# ETAP.net
KiCad netlist of a schematic drawn in EAGLE
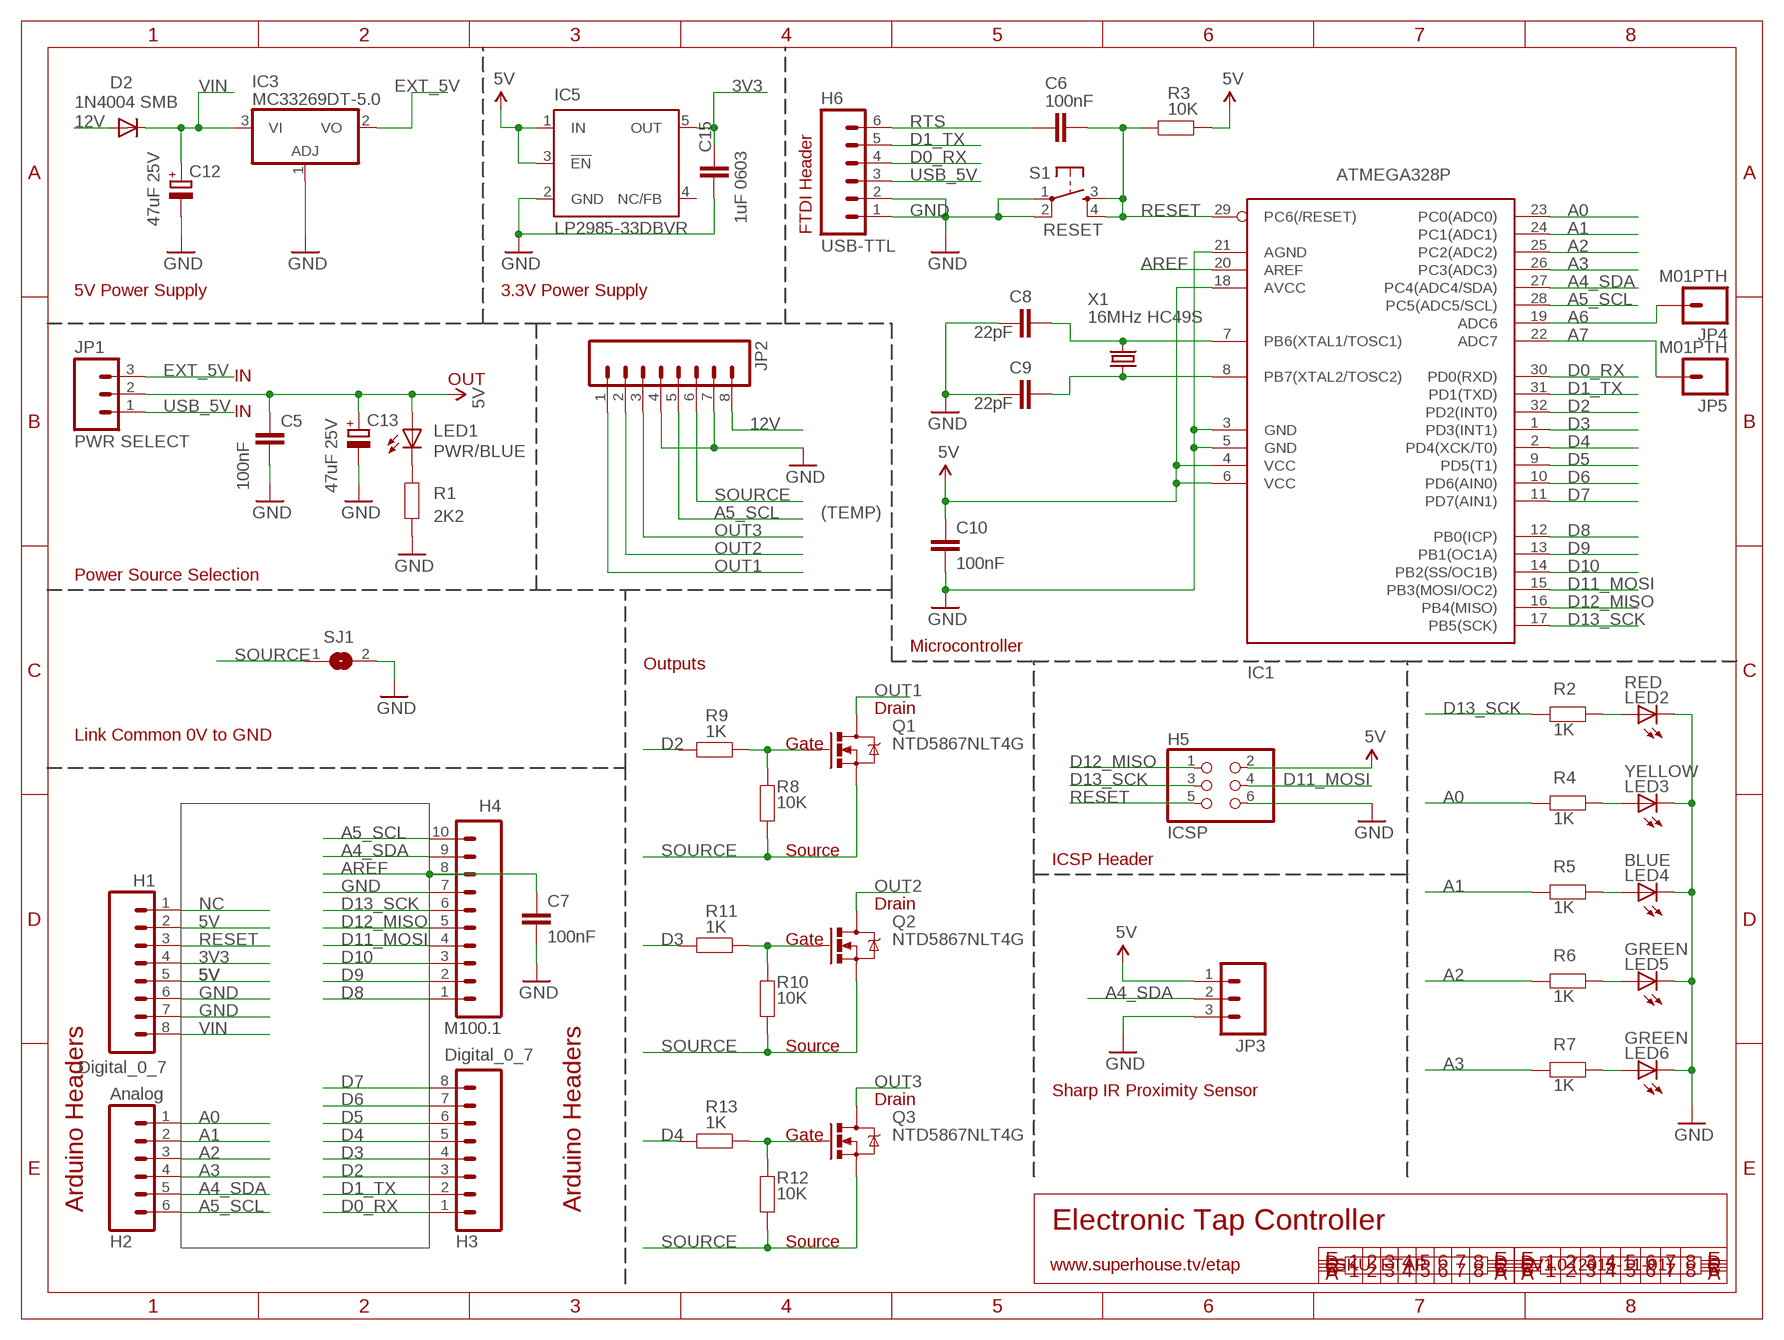
[diagram p0: schematic, sheet 1]

(export (version "E")
  (design (tool "Eeschema 10.0.6"))
  (components
    (comp (ref "C5")
      (value "100nF")
      (footprint "eagle-import:0603")
      (libsource (lib "eagle-import") (part "freetronics-master-v1.1_CAP0603"))
    )
    (comp (ref "C6")
      (value "100nF")
      (footprint "eagle-import:0603")
      (libsource (lib "eagle-import") (part "freetronics-master-v1.1_CAP0603"))
    )
    (comp (ref "C7")
      (value "100nF")
      (footprint "eagle-import:0603")
      (libsource (lib "eagle-import") (part "freetronics-master-v1.1_CAP0603"))
    )
    (comp (ref "C8")
      (value "22pF")
      (footprint "eagle-import:0603")
      (libsource (lib "eagle-import") (part "freetronics-master-v1.1_CAP0603"))
    )
    (comp (ref "C9")
      (value "22pF")
      (footprint "eagle-import:0603")
      (libsource (lib "eagle-import") (part "freetronics-master-v1.1_CAP0603"))
    )
    (comp (ref "C10")
      (value "100nF")
      (footprint "eagle-import:0603")
      (libsource (lib "eagle-import") (part "freetronics-master-v1.1_CAP0603"))
    )
    (comp (ref "C12")
      (value "47uF 25V")
      (footprint "eagle-import:PANASONIC_D")
      (libsource (lib "eagle-import") (part "CPOL-EUD"))
    )
    (comp (ref "C13")
      (value "47uF 25V")
      (footprint "eagle-import:PANASONIC_D")
      (libsource (lib "eagle-import") (part "CPOL-EUD"))
    )
    (comp (ref "C15")
      (value "1uF 0603")
      (footprint "eagle-import:0603")
      (libsource (lib "eagle-import") (part "CAP0603"))
    )
    (comp (ref "D2")
      (value "1N4004 SMB")
      (footprint "eagle-import:SMB-DIODE")
      (libsource (lib "eagle-import") (part "DIODESMB"))
    )
    (comp (ref "H1")
      (value "Digital_0_7")
      (footprint "eagle-import:1X08")
      (libsource (lib "eagle-import") (part "M08"))
    )
    (comp (ref "H2")
      (value "Analog")
      (footprint "eagle-import:1X06")
      (libsource (lib "eagle-import") (part "M06SIP"))
    )
    (comp (ref "H3")
      (value "Digital_0_7")
      (footprint "eagle-import:1X08")
      (libsource (lib "eagle-import") (part "M08"))
    )
    (comp (ref "H4")
      (value "M100.1")
      (footprint "eagle-import:1X10")
      (libsource (lib "eagle-import") (part "M100.1"))
    )
    (comp (ref "H5")
      (value "ICSP")
      (footprint "eagle-import:2X03")
      (libsource (lib "eagle-import") (part "PINHD-2X3"))
    )
    (comp (ref "H6")
      (value "USB-TTL")
      (footprint "eagle-import:1X06")
      (libsource (lib "eagle-import") (part "M06SIP"))
    )
    (comp (ref "IC1")
      (value "ATMEGA328P")
      (footprint "eagle-import:TQFP32-08")
      (libsource (lib "eagle-import") (part "AVR-MEGA8-AI"))
    )
    (comp (ref "IC3")
      (value "MC33269DT-5.0")
      (footprint "eagle-import:DPACK")
      (libsource (lib "eagle-import") (part "MC33269?D-5.0"))
    )
    (comp (ref "IC5")
      (value "LP2985-33DBVR")
      (footprint "eagle-import:TEXAS_SOT23-DBV")
      (libsource (lib "eagle-import") (part "TEXAS_TPS77033"))
    )
    (comp (ref "JP1")
      (value "PWR SELECT")
      (footprint "eagle-import:1X03")
      (libsource (lib "eagle-import") (part "M03PTH"))
    )
    (comp (ref "JP2")
      (value "M08STD")
      (footprint "eagle-import:1X08")
      (libsource (lib "eagle-import") (part "M08STD"))
    )
    (comp (ref "JP3")
      (value "M03PTH")
      (footprint "eagle-import:1X03")
      (libsource (lib "eagle-import") (part "freetronics-jon_M03PTH"))
    )
    (comp (ref "JP4")
      (value "M01PTH")
      (footprint "eagle-import:1X01")
      (libsource (lib "eagle-import") (part "M01PTH"))
    )
    (comp (ref "JP5")
      (value "M01PTH")
      (footprint "eagle-import:1X01")
      (libsource (lib "eagle-import") (part "M01PTH"))
    )
    (comp (ref "LED1")
      (value "PWR/BLUE")
      (footprint "eagle-import:LED-0603")
      (libsource (lib "eagle-import") (part "freetronics-jon_LED0603"))
    )
    (comp (ref "LED2")
      (value "RED")
      (footprint "eagle-import:LED3MM")
      (libsource (lib "eagle-import") (part "LED3MM"))
    )
    (comp (ref "LED3")
      (value "YELLOW")
      (footprint "eagle-import:LED3MM")
      (libsource (lib "eagle-import") (part "LED3MM"))
    )
    (comp (ref "LED4")
      (value "BLUE")
      (footprint "eagle-import:LED3MM")
      (libsource (lib "eagle-import") (part "LED3MM"))
    )
    (comp (ref "LED5")
      (value "GREEN")
      (footprint "eagle-import:LED3MM")
      (libsource (lib "eagle-import") (part "LED3MM"))
    )
    (comp (ref "LED6")
      (value "GREEN")
      (footprint "eagle-import:LED3MM")
      (libsource (lib "eagle-import") (part "LED3MM"))
    )
    (comp (ref "Q1")
      (value "NTD5867NLT4G")
      (footprint "eagle-import:DPACK")
      (libsource (lib "eagle-import") (part "MOSFET-NCHANNELDPAK"))
    )
    (comp (ref "Q2")
      (value "NTD5867NLT4G")
      (footprint "eagle-import:DPACK")
      (libsource (lib "eagle-import") (part "MOSFET-NCHANNELDPAK"))
    )
    (comp (ref "Q3")
      (value "NTD5867NLT4G")
      (footprint "eagle-import:DPACK")
      (libsource (lib "eagle-import") (part "MOSFET-NCHANNELDPAK"))
    )
    (comp (ref "R1")
      (value "2K2")
      (footprint "eagle-import:0603")
      (libsource (lib "eagle-import") (part "freetronics-master-v1.1_RESISTOR0603"))
    )
    (comp (ref "R2")
      (value "1K")
      (footprint "eagle-import:0603")
      (libsource (lib "eagle-import") (part "freetronics-master-v1.1_RESISTOR0603"))
    )
    (comp (ref "R3")
      (value "10K")
      (footprint "eagle-import:0603")
      (libsource (lib "eagle-import") (part "freetronics-master-v1.1_RESISTOR0603"))
    )
    (comp (ref "R4")
      (value "1K")
      (footprint "eagle-import:0603")
      (libsource (lib "eagle-import") (part "freetronics-master-v1.1_RESISTOR0603"))
    )
    (comp (ref "R5")
      (value "1K")
      (footprint "eagle-import:0603")
      (libsource (lib "eagle-import") (part "freetronics-master-v1.1_RESISTOR0603"))
    )
    (comp (ref "R6")
      (value "1K")
      (footprint "eagle-import:0603")
      (libsource (lib "eagle-import") (part "freetronics-master-v1.1_RESISTOR0603"))
    )
    (comp (ref "R7")
      (value "1K")
      (footprint "eagle-import:0603")
      (libsource (lib "eagle-import") (part "freetronics-master-v1.1_RESISTOR0603"))
    )
    (comp (ref "R8")
      (value "10K")
      (footprint "eagle-import:0603")
      (libsource (lib "eagle-import") (part "RESISTOR0603"))
    )
    (comp (ref "R9")
      (value "1K")
      (footprint "eagle-import:0603")
      (libsource (lib "eagle-import") (part "RESISTOR0603"))
    )
    (comp (ref "R10")
      (value "10K")
      (footprint "eagle-import:0603")
      (libsource (lib "eagle-import") (part "RESISTOR0603"))
    )
    (comp (ref "R11")
      (value "1K")
      (footprint "eagle-import:0603")
      (libsource (lib "eagle-import") (part "RESISTOR0603"))
    )
    (comp (ref "R12")
      (value "10K")
      (footprint "eagle-import:0603")
      (libsource (lib "eagle-import") (part "RESISTOR0603"))
    )
    (comp (ref "R13")
      (value "1K")
      (footprint "eagle-import:0603")
      (libsource (lib "eagle-import") (part "RESISTOR0603"))
    )
    (comp (ref "S1")
      (value "RESET")
      (footprint "eagle-import:TACTILE-PTH")
      (libsource (lib "eagle-import") (part "TAC_SWITCHPTH"))
    )
    (comp (ref "SJ1") (value "SJ") (footprint "eagle-import:SJ") (libsource (lib "eagle-import") (part "SJ")))
    (comp (ref "X1")
      (value "16MHz HC49S")
      (footprint "eagle-import:HC49U-V")
      (libsource (lib "eagle-import") (part "CRYSTALHC49UV"))
    )
  )
  (nets
    (net (code "1") (name "/3V3") (class "Default")
      (node (ref "C15") (pin "2") (pinfunction "2_2") (pintype "passive"))
      (node (ref "H1") (pin "4") (pinfunction "4_4") (pintype "passive"))
      (node (ref "IC5") (pin "5") (pinfunction "OUT_5") (pintype "passive"))
    )
    (net (code "2") (name "/12V") (class "Default")
      (node (ref "D2") (pin "A") (pinfunction "A_A") (pintype "passive"))
      (node (ref "JP2") (pin "8") (pinfunction "8_8") (pintype "passive"))
    )
    (net (code "3") (name "/A0") (class "Default")
      (node (ref "H2") (pin "1") (pinfunction "1_1") (pintype "passive"))
      (node (ref "IC1") (pin "23") (pinfunction "PC0(ADC0)_23") (pintype "bidirectional"))
      (node (ref "R4") (pin "2") (pinfunction "2_2") (pintype "passive"))
    )
    (net (code "4") (name "/A1") (class "Default")
      (node (ref "H2") (pin "2") (pinfunction "2_2") (pintype "passive"))
      (node (ref "IC1") (pin "24") (pinfunction "PC1(ADC1)_24") (pintype "bidirectional"))
      (node (ref "R5") (pin "2") (pinfunction "2_2") (pintype "passive"))
    )
    (net (code "5") (name "/A2") (class "Default")
      (node (ref "H2") (pin "3") (pinfunction "3_3") (pintype "passive"))
      (node (ref "IC1") (pin "25") (pinfunction "PC2(ADC2)_25") (pintype "bidirectional"))
      (node (ref "R6") (pin "2") (pinfunction "2_2") (pintype "passive"))
    )
    (net (code "6") (name "/A3") (class "Default")
      (node (ref "H2") (pin "4") (pinfunction "4_4") (pintype "passive"))
      (node (ref "IC1") (pin "26") (pinfunction "PC3(ADC3)_26") (pintype "bidirectional"))
      (node (ref "R7") (pin "2") (pinfunction "2_2") (pintype "passive"))
    )
    (net (code "7") (name "/A4_SDA") (class "Default")
      (node (ref "H2") (pin "5") (pinfunction "5_5") (pintype "passive"))
      (node (ref "H4") (pin "9") (pinfunction "9_9") (pintype "passive"))
      (node (ref "IC1") (pin "27") (pinfunction "PC4(ADC4/SDA)_27") (pintype "bidirectional"))
      (node (ref "JP3") (pin "2") (pinfunction "2_2") (pintype "passive"))
    )
    (net (code "8") (name "/A5_SCL") (class "Default")
      (node (ref "H2") (pin "6") (pinfunction "6_6") (pintype "passive"))
      (node (ref "H4") (pin "10") (pinfunction "10_10") (pintype "passive"))
      (node (ref "IC1") (pin "28") (pinfunction "PC5(ADC5/SCL)_28") (pintype "bidirectional"))
      (node (ref "JP2") (pin "5") (pinfunction "5_5") (pintype "passive"))
    )
    (net (code "9") (name "/A6") (class "Default")
      (node (ref "IC1") (pin "19") (pinfunction "ADC6_19") (pintype "bidirectional"))
      (node (ref "JP4") (pin "1") (pinfunction "1_1") (pintype "passive"))
    )
    (net (code "10") (name "/A7") (class "Default")
      (node (ref "IC1") (pin "22") (pinfunction "ADC7_22") (pintype "bidirectional"))
      (node (ref "JP5") (pin "1") (pinfunction "1_1") (pintype "passive"))
    )
    (net (code "11") (name "/AREF") (class "Default")
      (node (ref "C7") (pin "1") (pinfunction "1_1") (pintype "passive"))
      (node (ref "H4") (pin "8") (pinfunction "8_8") (pintype "passive"))
      (node (ref "IC1") (pin "20") (pinfunction "AREF_20") (pintype "bidirectional"))
    )
    (net (code "12") (name "/D0_RX") (class "Default")
      (node (ref "H3") (pin "1") (pinfunction "1_1") (pintype "passive"))
      (node (ref "H6") (pin "4") (pinfunction "4_4") (pintype "passive"))
      (node (ref "IC1") (pin "30") (pinfunction "PD0(RXD)_30") (pintype "bidirectional"))
    )
    (net (code "13") (name "/D1_TX") (class "Default")
      (node (ref "H3") (pin "2") (pinfunction "2_2") (pintype "passive"))
      (node (ref "H6") (pin "5") (pinfunction "5_5") (pintype "passive"))
      (node (ref "IC1") (pin "31") (pinfunction "PD1(TXD)_31") (pintype "bidirectional"))
    )
    (net (code "14") (name "/D2") (class "Default")
      (node (ref "H3") (pin "3") (pinfunction "3_3") (pintype "passive"))
      (node (ref "IC1") (pin "32") (pinfunction "PD2(INT0)_32") (pintype "bidirectional"))
      (node (ref "R9") (pin "2") (pinfunction "2_2") (pintype "passive"))
    )
    (net (code "15") (name "/D3") (class "Default")
      (node (ref "H3") (pin "4") (pinfunction "4_4") (pintype "passive"))
      (node (ref "IC1") (pin "1") (pinfunction "PD3(INT1)_1") (pintype "bidirectional"))
      (node (ref "R11") (pin "2") (pinfunction "2_2") (pintype "passive"))
    )
    (net (code "16") (name "/D4") (class "Default")
      (node (ref "H3") (pin "5") (pinfunction "5_5") (pintype "passive"))
      (node (ref "IC1") (pin "2") (pinfunction "PD4(XCK/T0)_2") (pintype "bidirectional"))
      (node (ref "R13") (pin "2") (pinfunction "2_2") (pintype "passive"))
    )
    (net (code "17") (name "/D5") (class "Default")
      (node (ref "H3") (pin "6") (pinfunction "6_6") (pintype "passive"))
      (node (ref "IC1") (pin "9") (pinfunction "PD5(T1)_9") (pintype "bidirectional"))
    )
    (net (code "18") (name "/D6") (class "Default")
      (node (ref "H3") (pin "7") (pinfunction "7_7") (pintype "passive"))
      (node (ref "IC1") (pin "10") (pinfunction "PD6(AIN0)_10") (pintype "bidirectional"))
    )
    (net (code "19") (name "/D7") (class "Default")
      (node (ref "H3") (pin "8") (pinfunction "8_8") (pintype "passive"))
      (node (ref "IC1") (pin "11") (pinfunction "PD7(AIN1)_11") (pintype "bidirectional"))
    )
    (net (code "20") (name "/D8") (class "Default")
      (node (ref "H4") (pin "1") (pinfunction "1_1") (pintype "passive"))
      (node (ref "IC1") (pin "12") (pinfunction "PB0(ICP)_12") (pintype "bidirectional"))
    )
    (net (code "21") (name "/D9") (class "Default")
      (node (ref "H4") (pin "2") (pinfunction "2_2") (pintype "passive"))
      (node (ref "IC1") (pin "13") (pinfunction "PB1(OC1A)_13") (pintype "bidirectional"))
    )
    (net (code "22") (name "/D10") (class "Default")
      (node (ref "H4") (pin "3") (pinfunction "3_3") (pintype "passive"))
      (node (ref "IC1") (pin "14") (pinfunction "PB2(SS/OC1B)_14") (pintype "bidirectional"))
    )
    (net (code "23") (name "/D11_MOSI") (class "Default")
      (node (ref "H4") (pin "4") (pinfunction "4_4") (pintype "passive"))
      (node (ref "H5") (pin "4") (pinfunction "4_4") (pintype "passive"))
      (node (ref "IC1") (pin "15") (pinfunction "PB3(MOSI/OC2)_15") (pintype "bidirectional"))
    )
    (net (code "24") (name "/D12_MISO") (class "Default")
      (node (ref "H4") (pin "5") (pinfunction "5_5") (pintype "passive"))
      (node (ref "H5") (pin "1") (pinfunction "1_1") (pintype "passive"))
      (node (ref "IC1") (pin "16") (pinfunction "PB4(MISO)_16") (pintype "bidirectional"))
    )
    (net (code "25") (name "/D13_SCK") (class "Default")
      (node (ref "H4") (pin "6") (pinfunction "6_6") (pintype "passive"))
      (node (ref "H5") (pin "3") (pinfunction "3_3") (pintype "passive"))
      (node (ref "IC1") (pin "17") (pinfunction "PB5(SCK)_17") (pintype "bidirectional"))
      (node (ref "R2") (pin "2") (pinfunction "2_2") (pintype "passive"))
    )
    (net (code "26") (name "/EXT_5V") (class "Default")
      (node (ref "IC3") (pin "2") (pinfunction "VO_2") (pintype "passive"))
      (node (ref "JP1") (pin "3") (pinfunction "3_3") (pintype "passive"))
    )
    (net (code "27") (name "/NC") (class "Default")
      (node (ref "H1") (pin "1") (pinfunction "1_1") (pintype "passive"))
    )
    (net (code "28") (name "/OUT1") (class "Default")
      (node (ref "JP2") (pin "1") (pinfunction "1_1") (pintype "passive"))
      (node (ref "Q1") (pin "2") (pinfunction "D_2") (pintype "passive"))
    )
    (net (code "29") (name "/OUT2") (class "Default")
      (node (ref "JP2") (pin "2") (pinfunction "2_2") (pintype "passive"))
      (node (ref "Q2") (pin "2") (pinfunction "D_2") (pintype "passive"))
    )
    (net (code "30") (name "/OUT3") (class "Default")
      (node (ref "JP2") (pin "3") (pinfunction "3_3") (pintype "passive"))
      (node (ref "Q3") (pin "2") (pinfunction "D_2") (pintype "passive"))
    )
    (net (code "31") (name "/RESET") (class "Default")
      (node (ref "C6") (pin "2") (pinfunction "2_2") (pintype "passive"))
      (node (ref "H1") (pin "3") (pinfunction "3_3") (pintype "passive"))
      (node (ref "H5") (pin "5") (pinfunction "5_5") (pintype "passive"))
      (node (ref "IC1") (pin "29") (pinfunction "PC6(/RESET)_29") (pintype "bidirectional"))
      (node (ref "R3") (pin "1") (pinfunction "1_1") (pintype "passive"))
      (node (ref "S1") (pin "3") (pinfunction "3_3") (pintype "passive"))
      (node (ref "S1") (pin "4") (pinfunction "4_4") (pintype "passive"))
    )
    (net (code "32") (name "/RTS") (class "Default")
      (node (ref "C6") (pin "1") (pinfunction "1_1") (pintype "passive"))
      (node (ref "H6") (pin "6") (pinfunction "6_6") (pintype "passive"))
    )
    (net (code "33") (name "/SOURCE") (class "Default")
      (node (ref "JP2") (pin "6") (pinfunction "6_6") (pintype "passive"))
      (node (ref "Q1") (pin "3") (pinfunction "S_3") (pintype "passive"))
      (node (ref "Q2") (pin "3") (pinfunction "S_3") (pintype "passive"))
      (node (ref "Q3") (pin "3") (pinfunction "S_3") (pintype "passive"))
      (node (ref "R10") (pin "1") (pinfunction "1_1") (pintype "passive"))
      (node (ref "R12") (pin "1") (pinfunction "1_1") (pintype "passive"))
      (node (ref "R8") (pin "1") (pinfunction "1_1") (pintype "passive"))
      (node (ref "SJ1") (pin "1") (pinfunction "1_1") (pintype "passive"))
    )
    (net (code "34") (name "/USB_5V") (class "Default")
      (node (ref "H6") (pin "3") (pinfunction "3_3") (pintype "passive"))
      (node (ref "JP1") (pin "1") (pinfunction "1_1") (pintype "passive"))
    )
    (net (code "35") (name "/VIN") (class "Default")
      (node (ref "C12") (pin "+") (pinfunction "+_+") (pintype "passive"))
      (node (ref "D2") (pin "C") (pinfunction "C_C") (pintype "passive"))
      (node (ref "H1") (pin "8") (pinfunction "8_8") (pintype "passive"))
      (node (ref "IC3") (pin "3") (pinfunction "VI_3") (pintype "input"))
    )
    (net (code "36") (name "5V") (class "Default")
      (node (ref "C10") (pin "1") (pinfunction "1_1") (pintype "passive"))
      (node (ref "C13") (pin "+") (pinfunction "+_+") (pintype "passive"))
      (node (ref "C5") (pin "1") (pinfunction "1_1") (pintype "passive"))
      (node (ref "H1") (pin "2") (pinfunction "2_2") (pintype "passive"))
      (node (ref "H1") (pin "5") (pinfunction "5_5") (pintype "passive"))
      (node (ref "H5") (pin "2") (pinfunction "2_2") (pintype "passive"))
      (node (ref "IC1") (pin "18") (pinfunction "AVCC_18") (pintype "bidirectional"))
      (node (ref "IC1") (pin "4") (pinfunction "VCC_4") (pintype "bidirectional"))
      (node (ref "IC1") (pin "6") (pinfunction "VCC_6") (pintype "bidirectional"))
      (node (ref "IC5") (pin "1") (pinfunction "IN_1") (pintype "input"))
      (node (ref "IC5") (pin "3") (pinfunction "~{EN}_3") (pintype "input"))
      (node (ref "JP1") (pin "2") (pinfunction "2_2") (pintype "passive"))
      (node (ref "JP3") (pin "1") (pinfunction "1_1") (pintype "passive"))
      (node (ref "LED1") (pin "A") (pinfunction "A_A") (pintype "passive"))
      (node (ref "R3") (pin "2") (pinfunction "2_2") (pintype "passive"))
    )
    (net (code "37") (name "GND") (class "Default")
      (node (ref "C10") (pin "2") (pinfunction "2_2") (pintype "passive"))
      (node (ref "C12") (pin "-") (pinfunction "-_-") (pintype "passive"))
      (node (ref "C13") (pin "-") (pinfunction "-_-") (pintype "passive"))
      (node (ref "C15") (pin "1") (pinfunction "1_1") (pintype "passive"))
      (node (ref "C5") (pin "2") (pinfunction "2_2") (pintype "passive"))
      (node (ref "C7") (pin "2") (pinfunction "2_2") (pintype "passive"))
      (node (ref "C8") (pin "1") (pinfunction "1_1") (pintype "passive"))
      (node (ref "C9") (pin "1") (pinfunction "1_1") (pintype "passive"))
      (node (ref "H1") (pin "6") (pinfunction "6_6") (pintype "passive"))
      (node (ref "H1") (pin "7") (pinfunction "7_7") (pintype "passive"))
      (node (ref "H4") (pin "7") (pinfunction "7_7") (pintype "passive"))
      (node (ref "H5") (pin "6") (pinfunction "6_6") (pintype "passive"))
      (node (ref "H6") (pin "1") (pinfunction "1_1") (pintype "passive"))
      (node (ref "H6") (pin "2") (pinfunction "2_2") (pintype "passive"))
      (node (ref "IC1") (pin "21") (pinfunction "AGND_21") (pintype "bidirectional"))
      (node (ref "IC1") (pin "3") (pinfunction "GND_3") (pintype "bidirectional"))
      (node (ref "IC1") (pin "5") (pinfunction "GND_5") (pintype "bidirectional"))
      (node (ref "IC3") (pin "1") (pinfunction "ADJ_1") (pintype "input"))
      (node (ref "IC5") (pin "2") (pinfunction "GND_2") (pintype "power_in"))
      (node (ref "JP2") (pin "4") (pinfunction "4_4") (pintype "passive"))
      (node (ref "JP2") (pin "7") (pinfunction "7_7") (pintype "passive"))
      (node (ref "JP3") (pin "3") (pinfunction "3_3") (pintype "passive"))
      (node (ref "LED2") (pin "K") (pinfunction "C_K") (pintype "passive"))
      (node (ref "LED3") (pin "K") (pinfunction "C_K") (pintype "passive"))
      (node (ref "LED4") (pin "K") (pinfunction "C_K") (pintype "passive"))
      (node (ref "LED5") (pin "K") (pinfunction "C_K") (pintype "passive"))
      (node (ref "LED6") (pin "K") (pinfunction "C_K") (pintype "passive"))
      (node (ref "R1") (pin "1") (pinfunction "1_1") (pintype "passive"))
      (node (ref "S1") (pin "1") (pinfunction "1_1") (pintype "passive"))
      (node (ref "S1") (pin "2") (pinfunction "2_2") (pintype "passive"))
      (node (ref "SJ1") (pin "2") (pinfunction "2_2") (pintype "passive"))
    )
    (net (code "38") (name "Net-(IC1-PB6(XTAL1{slash}TOSC1))") (class "Default")
      (node (ref "C8") (pin "2") (pinfunction "2_2") (pintype "passive"))
      (node (ref "IC1") (pin "7") (pinfunction "PB6(XTAL1/TOSC1)_7") (pintype "bidirectional"))
      (node (ref "X1") (pin "2") (pinfunction "2_2") (pintype "passive"))
    )
    (net (code "39") (name "Net-(IC1-PB7(XTAL2{slash}TOSC2))") (class "Default")
      (node (ref "C9") (pin "2") (pinfunction "2_2") (pintype "passive"))
      (node (ref "IC1") (pin "8") (pinfunction "PB7(XTAL2/TOSC2)_8") (pintype "bidirectional"))
      (node (ref "X1") (pin "1") (pinfunction "1_1") (pintype "passive"))
    )
    (net (code "40") (name "Net-(LED1-PadC)") (class "Default")
      (node (ref "LED1") (pin "C") (pinfunction "C_C") (pintype "passive"))
      (node (ref "R1") (pin "2") (pinfunction "2_2") (pintype "passive"))
    )
    (net (code "41") (name "Net-(LED2-PadA)") (class "Default")
      (node (ref "LED2") (pin "A") (pinfunction "A_A") (pintype "passive"))
      (node (ref "R2") (pin "1") (pinfunction "1_1") (pintype "passive"))
    )
    (net (code "42") (name "Net-(LED3-PadA)") (class "Default")
      (node (ref "LED3") (pin "A") (pinfunction "A_A") (pintype "passive"))
      (node (ref "R4") (pin "1") (pinfunction "1_1") (pintype "passive"))
    )
    (net (code "43") (name "Net-(LED4-PadA)") (class "Default")
      (node (ref "LED4") (pin "A") (pinfunction "A_A") (pintype "passive"))
      (node (ref "R5") (pin "1") (pinfunction "1_1") (pintype "passive"))
    )
    (net (code "44") (name "Net-(LED5-PadA)") (class "Default")
      (node (ref "LED5") (pin "A") (pinfunction "A_A") (pintype "passive"))
      (node (ref "R6") (pin "1") (pinfunction "1_1") (pintype "passive"))
    )
    (net (code "45") (name "Net-(LED6-PadA)") (class "Default")
      (node (ref "LED6") (pin "A") (pinfunction "A_A") (pintype "passive"))
      (node (ref "R7") (pin "1") (pinfunction "1_1") (pintype "passive"))
    )
    (net (code "46") (name "Net-(Q1-G)") (class "Default")
      (node (ref "Q1") (pin "1") (pinfunction "G_1") (pintype "passive"))
      (node (ref "R8") (pin "2") (pinfunction "2_2") (pintype "passive"))
      (node (ref "R9") (pin "1") (pinfunction "1_1") (pintype "passive"))
    )
    (net (code "47") (name "Net-(Q2-G)") (class "Default")
      (node (ref "Q2") (pin "1") (pinfunction "G_1") (pintype "passive"))
      (node (ref "R10") (pin "2") (pinfunction "2_2") (pintype "passive"))
      (node (ref "R11") (pin "1") (pinfunction "1_1") (pintype "passive"))
    )
    (net (code "48") (name "Net-(Q3-G)") (class "Default")
      (node (ref "Q3") (pin "1") (pinfunction "G_1") (pintype "passive"))
      (node (ref "R12") (pin "2") (pinfunction "2_2") (pintype "passive"))
      (node (ref "R13") (pin "1") (pinfunction "1_1") (pintype "passive"))
    )
    (net (code "49") (name "unconnected-(IC5-NC{slash}FB-Pad4)") (class "Default")
      (node (ref "IC5") (pin "4") (pinfunction "NC/FB_4") (pintype "passive"))
    )
  )
)
